# Frontboard_Xtended.net
KiCad netlist of a schematic drawn in EAGLE
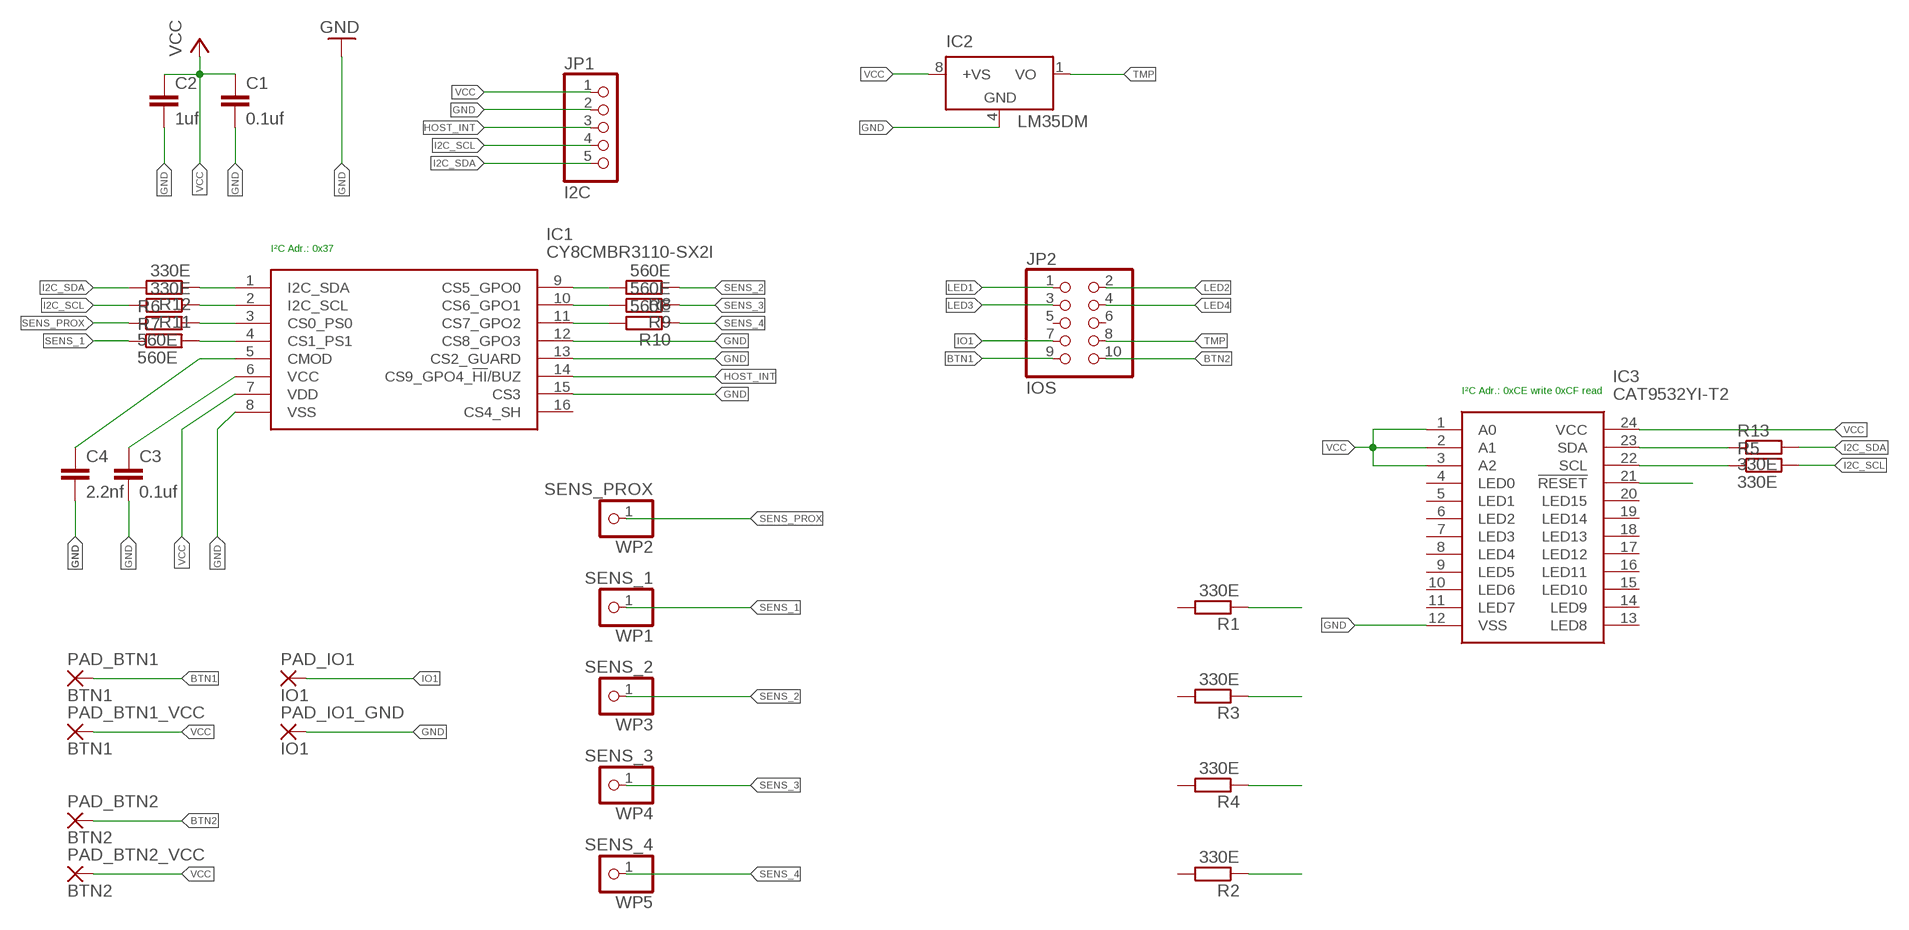
[diagram p0: schematic, sheet 1]

(export (version "E")
  (design (tool "Eeschema 10.0.6"))
  (components
    (comp (ref "C1")
      (value "0.1uf")
      (footprint "eagle-import:C2220K")
      (libsource (lib "eagle-import") (part "C-EUC2220K"))
    )
    (comp (ref "C2")
      (value "1uf")
      (footprint "eagle-import:C2220K")
      (libsource (lib "eagle-import") (part "C-EUC2220K"))
    )
    (comp (ref "C3")
      (value "0.1uf")
      (footprint "eagle-import:C2220K")
      (libsource (lib "eagle-import") (part "C-EUC2220K"))
    )
    (comp (ref "C4")
      (value "2.2nf")
      (footprint "eagle-import:C2220K")
      (libsource (lib "eagle-import") (part "C-EUC2220K"))
    )
    (comp (ref "IC1")
      (value "CY8CMBR3110-SX2I")
      (footprint "eagle-import:SOIC127P600X173-16N")
      (fields (field (name "RS_PART_NUMBER") "1242975P"))
      (libsource (lib "eagle-import") (part "CY8CMBR3110-SX2I"))
    )
    (comp (ref "IC2")
      (value "LM35DM")
      (footprint "eagle-import:SO08")
      (libsource (lib "eagle-import") (part "LM35DM"))
    )
    (comp (ref "IC3")
      (value "CAT9532YI-T2")
      (footprint "eagle-import:SOP65P640X120-24N")
      (libsource (lib "eagle-import") (part "CAT9532YI-T2"))
    )
    (comp (ref "JP1")
      (value "I2C")
      (footprint "eagle-import:1X05SMD")
      (libsource (lib "eagle-import") (part "PINHD-1X5_2.54-SMD"))
    )
    (comp (ref "JP2")
      (value "IOS")
      (footprint "eagle-import:2X05SMD")
      (libsource (lib "eagle-import") (part "PINHD-2X5_2.54-SMD"))
    )
    (comp (ref "PAD_BTN1")
      (value "BTN1")
      (footprint "eagle-import:2,54_1,0")
      (libsource (lib "eagle-import") (part "2,54/1,0"))
    )
    (comp (ref "PAD_BTN1_VCC")
      (value "BTN1")
      (footprint "eagle-import:2,54_1,0")
      (libsource (lib "eagle-import") (part "2,54/1,0"))
    )
    (comp (ref "PAD_BTN2")
      (value "BTN2")
      (footprint "eagle-import:2,54_1,0")
      (libsource (lib "eagle-import") (part "2,54/1,0"))
    )
    (comp (ref "PAD_BTN2_VCC")
      (value "BTN2")
      (footprint "eagle-import:2,54_1,0")
      (libsource (lib "eagle-import") (part "2,54/1,0"))
    )
    (comp (ref "PAD_IO1")
      (value "IO1")
      (footprint "eagle-import:2,54_1,0")
      (libsource (lib "eagle-import") (part "2,54/1,0"))
    )
    (comp (ref "PAD_IO1_GND")
      (value "IO1")
      (footprint "eagle-import:2,54_1,0")
      (libsource (lib "eagle-import") (part "2,54/1,0"))
    )
    (comp (ref "R1")
      (value "330E")
      (footprint "eagle-import:R2010")
      (libsource (lib "eagle-import") (part "R-EU_R2010"))
    )
    (comp (ref "R2")
      (value "330E")
      (footprint "eagle-import:R2010")
      (libsource (lib "eagle-import") (part "R-EU_R2010"))
    )
    (comp (ref "R3")
      (value "330E")
      (footprint "eagle-import:R2010")
      (libsource (lib "eagle-import") (part "R-EU_R2010"))
    )
    (comp (ref "R4")
      (value "330E")
      (footprint "eagle-import:R2010")
      (libsource (lib "eagle-import") (part "R-EU_R2010"))
    )
    (comp (ref "R5")
      (value "330E")
      (footprint "eagle-import:R2010")
      (libsource (lib "eagle-import") (part "R-EU_R2010"))
    )
    (comp (ref "R6")
      (value "560E")
      (footprint "eagle-import:R2010")
      (libsource (lib "eagle-import") (part "R-EU_R2010"))
    )
    (comp (ref "R7")
      (value "560E")
      (footprint "eagle-import:R2010")
      (libsource (lib "eagle-import") (part "R-EU_R2010"))
    )
    (comp (ref "R8")
      (value "560E")
      (footprint "eagle-import:R2010")
      (libsource (lib "eagle-import") (part "R-EU_R2010"))
    )
    (comp (ref "R9")
      (value "560E")
      (footprint "eagle-import:R2010")
      (libsource (lib "eagle-import") (part "R-EU_R2010"))
    )
    (comp (ref "R10")
      (value "560E")
      (footprint "eagle-import:R2010")
      (libsource (lib "eagle-import") (part "R-EU_R2010"))
    )
    (comp (ref "R11")
      (value "330E")
      (footprint "eagle-import:R2010")
      (libsource (lib "eagle-import") (part "R-EU_R2010"))
    )
    (comp (ref "R12")
      (value "330E")
      (footprint "eagle-import:R2010")
      (libsource (lib "eagle-import") (part "R-EU_R2010"))
    )
    (comp (ref "R13")
      (value "330E")
      (footprint "eagle-import:R2010")
      (libsource (lib "eagle-import") (part "R-EU_R2010"))
    )
    (comp (ref "WP1")
      (value "SENS_1")
      (footprint "eagle-import:WPAD-1-0603")
      (libsource (lib "eagle-import") (part "WPAD-1-0603"))
    )
    (comp (ref "WP2")
      (value "SENS_PROX")
      (footprint "eagle-import:WPAD-1-0603")
      (libsource (lib "eagle-import") (part "WPAD-1-0603"))
    )
    (comp (ref "WP3")
      (value "SENS_2")
      (footprint "eagle-import:WPAD-1-0603")
      (libsource (lib "eagle-import") (part "WPAD-1-0603"))
    )
    (comp (ref "WP4")
      (value "SENS_3")
      (footprint "eagle-import:WPAD-1-0603")
      (libsource (lib "eagle-import") (part "WPAD-1-0603"))
    )
    (comp (ref "WP5")
      (value "SENS_4")
      (footprint "eagle-import:WPAD-1-0603")
      (libsource (lib "eagle-import") (part "WPAD-1-0603"))
    )
  )
  (nets
    (net (code "1") (name "BTN1") (class "Default")
      (node (ref "JP2") (pin "9") (pinfunction "9_9") (pintype "passive"))
      (node (ref "PAD_BTN1") (pin "1") (pinfunction "P_1") (pintype "passive"))
    )
    (net (code "2") (name "BTN2") (class "Default")
      (node (ref "JP2") (pin "10") (pinfunction "10_10") (pintype "passive"))
      (node (ref "PAD_BTN2") (pin "1") (pinfunction "P_1") (pintype "passive"))
    )
    (net (code "3") (name "GND") (class "Default")
      (node (ref "C1") (pin "2") (pinfunction "2_2") (pintype "passive"))
      (node (ref "C2") (pin "2") (pinfunction "2_2") (pintype "passive"))
      (node (ref "C3") (pin "2") (pinfunction "2_2") (pintype "passive"))
      (node (ref "C4") (pin "2") (pinfunction "2_2") (pintype "passive"))
      (node (ref "IC1") (pin "12") (pinfunction "CS8_GPO3_12") (pintype "bidirectional"))
      (node (ref "IC1") (pin "13") (pinfunction "CS2_GUARD_13") (pintype "bidirectional"))
      (node (ref "IC1") (pin "15") (pinfunction "CS3_15") (pintype "bidirectional"))
      (node (ref "IC1") (pin "8") (pinfunction "VSS_8") (pintype "bidirectional"))
      (node (ref "IC2") (pin "4") (pinfunction "GND_4") (pintype "power_in"))
      (node (ref "IC3") (pin "12") (pinfunction "VSS_12") (pintype "power_in"))
      (node (ref "JP1") (pin "2") (pinfunction "2_2") (pintype "passive"))
      (node (ref "PAD_IO1_GND") (pin "1") (pinfunction "P_1") (pintype "passive"))
    )
    (net (code "4") (name "HOST_INT") (class "Default")
      (node (ref "IC1") (pin "14") (pinfunction "CS9_GPO4_~{HI}/BUZ_14") (pintype "bidirectional"))
      (node (ref "JP1") (pin "3") (pinfunction "3_3") (pintype "passive"))
    )
    (net (code "5") (name "I2C_SCL") (class "Default")
      (node (ref "JP1") (pin "4") (pinfunction "4_4") (pintype "passive"))
      (node (ref "R11") (pin "2") (pinfunction "2_2") (pintype "passive"))
      (node (ref "R5") (pin "2") (pinfunction "2_2") (pintype "passive"))
    )
    (net (code "6") (name "I2C_SDA") (class "Default")
      (node (ref "JP1") (pin "5") (pinfunction "5_5") (pintype "passive"))
      (node (ref "R12") (pin "2") (pinfunction "2_2") (pintype "passive"))
      (node (ref "R13") (pin "2") (pinfunction "2_2") (pintype "passive"))
    )
    (net (code "7") (name "IO1") (class "Default")
      (node (ref "JP2") (pin "7") (pinfunction "7_7") (pintype "passive"))
      (node (ref "PAD_IO1") (pin "1") (pinfunction "P_1") (pintype "passive"))
    )
    (net (code "8") (name "LED1") (class "Default")
      (node (ref "JP2") (pin "1") (pinfunction "1_1") (pintype "passive"))
    )
    (net (code "9") (name "LED2") (class "Default")
      (node (ref "JP2") (pin "2") (pinfunction "2_2") (pintype "passive"))
    )
    (net (code "10") (name "LED3") (class "Default")
      (node (ref "JP2") (pin "3") (pinfunction "3_3") (pintype "passive"))
    )
    (net (code "11") (name "LED4") (class "Default")
      (node (ref "JP2") (pin "4") (pinfunction "4_4") (pintype "passive"))
    )
    (net (code "12") (name "Net-(IC1-CMOD)") (class "Default")
      (node (ref "C4") (pin "1") (pinfunction "1_1") (pintype "passive"))
      (node (ref "IC1") (pin "5") (pinfunction "CMOD_5") (pintype "bidirectional"))
    )
    (net (code "13") (name "Net-(IC1-CS0_PS0)") (class "Default")
      (node (ref "IC1") (pin "3") (pinfunction "CS0_PS0_3") (pintype "bidirectional"))
      (node (ref "R6") (pin "2") (pinfunction "2_2") (pintype "passive"))
    )
    (net (code "14") (name "Net-(IC1-CS1_PS1)") (class "Default")
      (node (ref "IC1") (pin "4") (pinfunction "CS1_PS1_4") (pintype "bidirectional"))
      (node (ref "R7") (pin "2") (pinfunction "2_2") (pintype "passive"))
    )
    (net (code "15") (name "Net-(IC1-CS5_GPO0)") (class "Default")
      (node (ref "IC1") (pin "9") (pinfunction "CS5_GPO0_9") (pintype "bidirectional"))
      (node (ref "R8") (pin "2") (pinfunction "2_2") (pintype "passive"))
    )
    (net (code "16") (name "Net-(IC1-CS6_GPO1)") (class "Default")
      (node (ref "IC1") (pin "10") (pinfunction "CS6_GPO1_10") (pintype "bidirectional"))
      (node (ref "R9") (pin "2") (pinfunction "2_2") (pintype "passive"))
    )
    (net (code "17") (name "Net-(IC1-CS7_GPO2)") (class "Default")
      (node (ref "IC1") (pin "11") (pinfunction "CS7_GPO2_11") (pintype "bidirectional"))
      (node (ref "R10") (pin "2") (pinfunction "2_2") (pintype "passive"))
    )
    (net (code "18") (name "Net-(IC1-I2C_SCL)") (class "Default")
      (node (ref "IC1") (pin "2") (pinfunction "I2C_SCL_2") (pintype "bidirectional"))
      (node (ref "R11") (pin "1") (pinfunction "1_1") (pintype "passive"))
    )
    (net (code "19") (name "Net-(IC1-I2C_SDA)") (class "Default")
      (node (ref "IC1") (pin "1") (pinfunction "I2C_SDA_1") (pintype "bidirectional"))
      (node (ref "R12") (pin "1") (pinfunction "1_1") (pintype "passive"))
    )
    (net (code "20") (name "Net-(IC1-VCC)") (class "Default")
      (node (ref "C3") (pin "1") (pinfunction "1_1") (pintype "passive"))
      (node (ref "IC1") (pin "6") (pinfunction "VCC_6") (pintype "bidirectional"))
    )
    (net (code "21") (name "Net-(IC3-SCL)") (class "Default")
      (node (ref "IC3") (pin "22") (pinfunction "SCL_22") (pintype "bidirectional"))
      (node (ref "R5") (pin "1") (pinfunction "1_1") (pintype "passive"))
    )
    (net (code "22") (name "Net-(IC3-SDA)") (class "Default")
      (node (ref "IC3") (pin "23") (pinfunction "SDA_23") (pintype "bidirectional"))
      (node (ref "R13") (pin "1") (pinfunction "1_1") (pintype "passive"))
    )
    (net (code "23") (name "SENS_1") (class "Default")
      (node (ref "R7") (pin "1") (pinfunction "1_1") (pintype "passive"))
      (node (ref "WP1") (pin "1") (pinfunction "1_1") (pintype "passive"))
    )
    (net (code "24") (name "SENS_2") (class "Default")
      (node (ref "R8") (pin "1") (pinfunction "1_1") (pintype "passive"))
      (node (ref "WP3") (pin "1") (pinfunction "1_1") (pintype "passive"))
    )
    (net (code "25") (name "SENS_3") (class "Default")
      (node (ref "R9") (pin "1") (pinfunction "1_1") (pintype "passive"))
      (node (ref "WP4") (pin "1") (pinfunction "1_1") (pintype "passive"))
    )
    (net (code "26") (name "SENS_4") (class "Default")
      (node (ref "R10") (pin "1") (pinfunction "1_1") (pintype "passive"))
      (node (ref "WP5") (pin "1") (pinfunction "1_1") (pintype "passive"))
    )
    (net (code "27") (name "SENS_PROX") (class "Default")
      (node (ref "R6") (pin "1") (pinfunction "1_1") (pintype "passive"))
      (node (ref "WP2") (pin "1") (pinfunction "1_1") (pintype "passive"))
    )
    (net (code "28") (name "TMP") (class "Default")
      (node (ref "IC2") (pin "1") (pinfunction "VO_1") (pintype "input"))
      (node (ref "JP2") (pin "8") (pinfunction "8_8") (pintype "passive"))
    )
    (net (code "29") (name "VCC") (class "Default")
      (node (ref "C1") (pin "1") (pinfunction "1_1") (pintype "passive"))
      (node (ref "C2") (pin "1") (pinfunction "1_1") (pintype "passive"))
      (node (ref "IC1") (pin "7") (pinfunction "VDD_7") (pintype "bidirectional"))
      (node (ref "IC2") (pin "8") (pinfunction "+VS_8") (pintype "input"))
      (node (ref "IC3") (pin "1") (pinfunction "A0_1") (pintype "input"))
      (node (ref "IC3") (pin "2") (pinfunction "A1_2") (pintype "input"))
      (node (ref "IC3") (pin "24") (pinfunction "VCC_24") (pintype "power_in"))
      (node (ref "IC3") (pin "3") (pinfunction "A2_3") (pintype "input"))
      (node (ref "JP1") (pin "1") (pinfunction "1_1") (pintype "passive"))
      (node (ref "PAD_BTN1_VCC") (pin "1") (pinfunction "P_1") (pintype "passive"))
      (node (ref "PAD_BTN2_VCC") (pin "1") (pinfunction "P_1") (pintype "passive"))
    )
    (net (code "30") (name "unconnected-(IC1-CS4_SH-Pad16)") (class "Default")
      (node (ref "IC1") (pin "16") (pinfunction "CS4_SH_16") (pintype "bidirectional"))
    )
    (net (code "31") (name "unconnected-(IC3-LED0-Pad4)") (class "Default")
      (node (ref "IC3") (pin "4") (pinfunction "LED0_4") (pintype "output"))
    )
    (net (code "32") (name "unconnected-(IC3-LED1-Pad5)") (class "Default")
      (node (ref "IC3") (pin "5") (pinfunction "LED1_5") (pintype "output"))
    )
    (net (code "33") (name "unconnected-(IC3-LED2-Pad6)") (class "Default")
      (node (ref "IC3") (pin "6") (pinfunction "LED2_6") (pintype "output"))
    )
    (net (code "34") (name "unconnected-(IC3-LED3-Pad7)") (class "Default")
      (node (ref "IC3") (pin "7") (pinfunction "LED3_7") (pintype "output"))
    )
    (net (code "35") (name "unconnected-(IC3-LED4-Pad8)") (class "Default")
      (node (ref "IC3") (pin "8") (pinfunction "LED4_8") (pintype "output"))
    )
    (net (code "36") (name "unconnected-(IC3-LED5-Pad9)") (class "Default")
      (node (ref "IC3") (pin "9") (pinfunction "LED5_9") (pintype "output"))
    )
    (net (code "37") (name "unconnected-(IC3-LED6-Pad10)") (class "Default")
      (node (ref "IC3") (pin "10") (pinfunction "LED6_10") (pintype "output"))
    )
    (net (code "38") (name "unconnected-(IC3-LED7-Pad11)") (class "Default")
      (node (ref "IC3") (pin "11") (pinfunction "LED7_11") (pintype "output"))
    )
    (net (code "39") (name "unconnected-(IC3-LED8-Pad13)") (class "Default")
      (node (ref "IC3") (pin "13") (pinfunction "LED8_13") (pintype "output"))
    )
    (net (code "40") (name "unconnected-(IC3-LED9-Pad14)") (class "Default")
      (node (ref "IC3") (pin "14") (pinfunction "LED9_14") (pintype "output"))
    )
    (net (code "41") (name "unconnected-(IC3-LED10-Pad15)") (class "Default")
      (node (ref "IC3") (pin "15") (pinfunction "LED10_15") (pintype "output"))
    )
    (net (code "42") (name "unconnected-(IC3-LED11-Pad16)") (class "Default")
      (node (ref "IC3") (pin "16") (pinfunction "LED11_16") (pintype "output"))
    )
    (net (code "43") (name "unconnected-(IC3-LED12-Pad17)") (class "Default")
      (node (ref "IC3") (pin "17") (pinfunction "LED12_17") (pintype "output"))
    )
    (net (code "44") (name "unconnected-(IC3-LED13-Pad18)") (class "Default")
      (node (ref "IC3") (pin "18") (pinfunction "LED13_18") (pintype "output"))
    )
    (net (code "45") (name "unconnected-(IC3-LED14-Pad19)") (class "Default")
      (node (ref "IC3") (pin "19") (pinfunction "LED14_19") (pintype "output"))
    )
    (net (code "46") (name "unconnected-(IC3-LED15-Pad20)") (class "Default")
      (node (ref "IC3") (pin "20") (pinfunction "LED15_20") (pintype "output"))
    )
    (net (code "47") (name "unconnected-(IC3-~{RESET}-Pad21)") (class "Default")
      (node (ref "IC3") (pin "21") (pinfunction "~{RESET}_21") (pintype "input"))
    )
    (net (code "48") (name "unconnected-(JP2-Pad5)") (class "Default")
      (node (ref "JP2") (pin "5") (pinfunction "5_5") (pintype "passive"))
    )
    (net (code "49") (name "unconnected-(JP2-Pad6)") (class "Default")
      (node (ref "JP2") (pin "6") (pinfunction "6_6") (pintype "passive"))
    )
    (net (code "50") (name "unconnected-(R1-Pad1)") (class "Default")
      (node (ref "R1") (pin "1") (pinfunction "1_1") (pintype "passive"))
    )
    (net (code "51") (name "unconnected-(R1-Pad2)") (class "Default")
      (node (ref "R1") (pin "2") (pinfunction "2_2") (pintype "passive"))
    )
    (net (code "52") (name "unconnected-(R2-Pad1)") (class "Default")
      (node (ref "R2") (pin "1") (pinfunction "1_1") (pintype "passive"))
    )
    (net (code "53") (name "unconnected-(R2-Pad2)") (class "Default")
      (node (ref "R2") (pin "2") (pinfunction "2_2") (pintype "passive"))
    )
    (net (code "54") (name "unconnected-(R3-Pad1)") (class "Default")
      (node (ref "R3") (pin "1") (pinfunction "1_1") (pintype "passive"))
    )
    (net (code "55") (name "unconnected-(R3-Pad2)") (class "Default")
      (node (ref "R3") (pin "2") (pinfunction "2_2") (pintype "passive"))
    )
    (net (code "56") (name "unconnected-(R4-Pad1)") (class "Default")
      (node (ref "R4") (pin "1") (pinfunction "1_1") (pintype "passive"))
    )
    (net (code "57") (name "unconnected-(R4-Pad2)") (class "Default")
      (node (ref "R4") (pin "2") (pinfunction "2_2") (pintype "passive"))
    )
  )
)
